# H18R2_Backend.net
KiCad netlist of a schematic drawn in Altium Designer
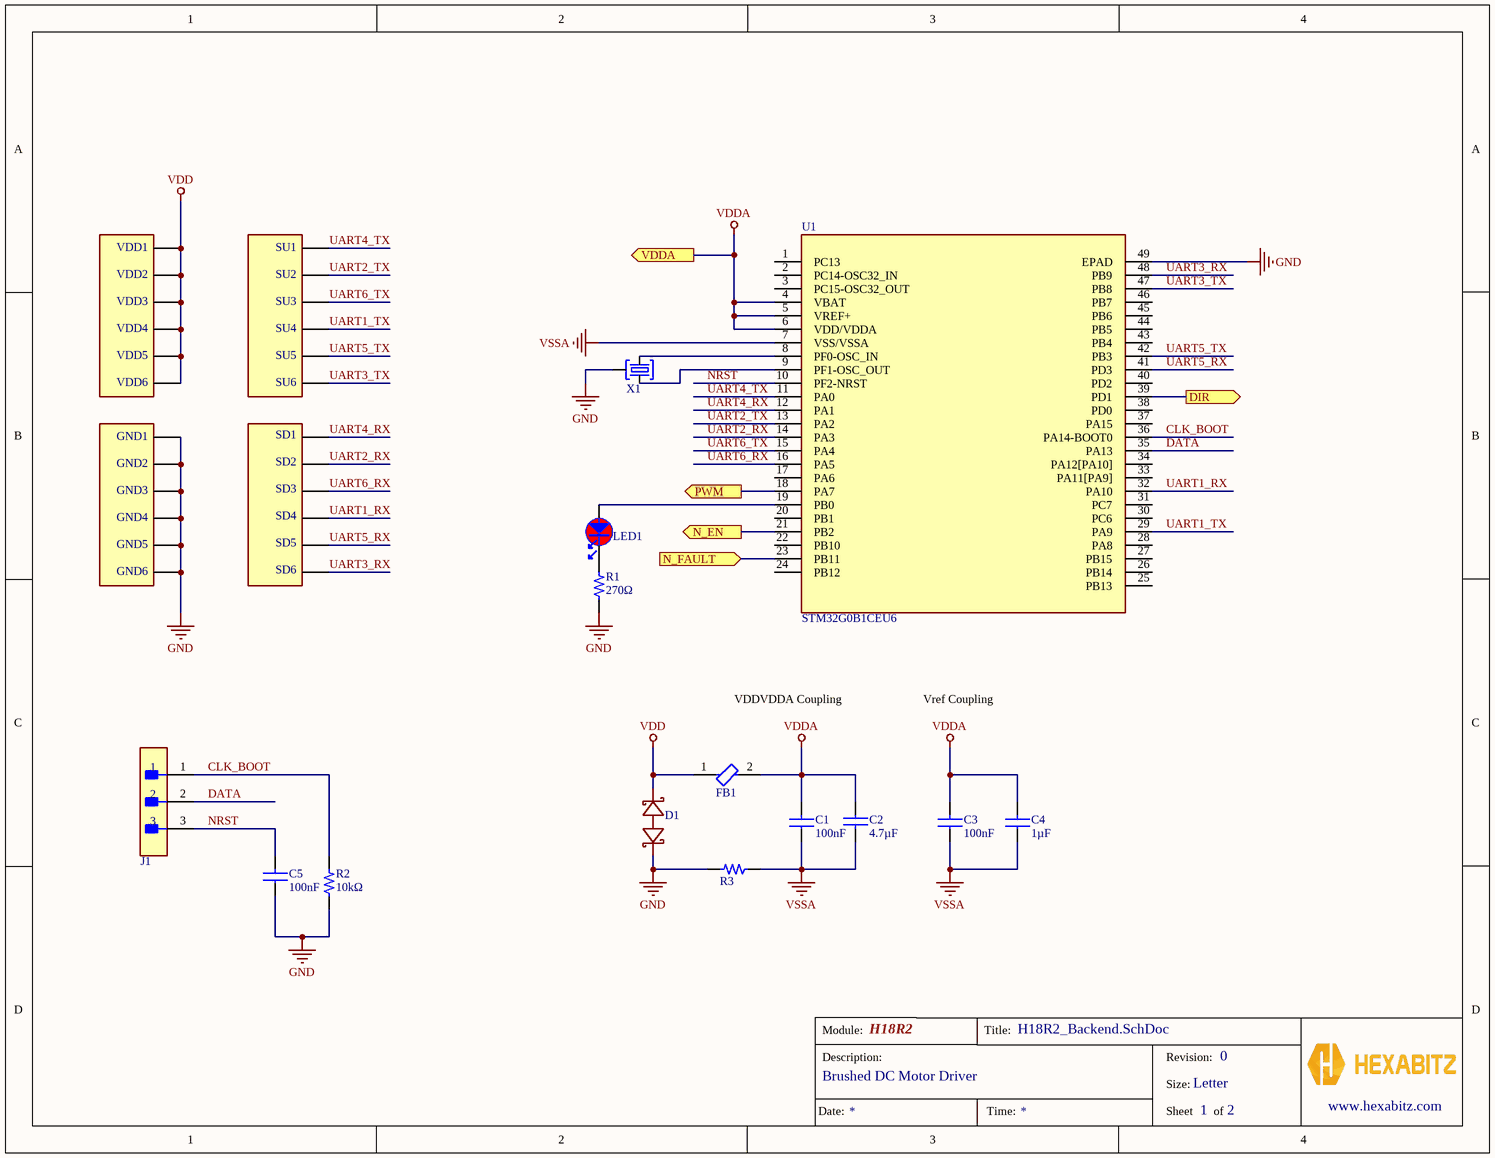
[diagram p0: H18R2_Backend.SchDoc]

(export (version "E")
  (design (tool "Eeschema 10.0.6"))
  (components
    (comp (ref "C1")
      (value "100nF")
      (footprint "C0603")
      (fields
        (field (name "MANUFACTURER") "Samsung Electro-Mechanics")
        (field (name "MANUFACTURER PART NUMBER") "CL10B104KA8NNNC")
        (field (name "TOLERANCE") "10%")
      )
      (libsource (lib "Hexabitz Altium Library") (part "generic Capacitor"))
    )
    (comp (ref "C2")
      (value "4.7µF")
      (footprint "C0805")
      (fields
        (field (name "MANUFACTURER") "Samsung Electro-Mechanics")
        (field (name "MANUFACTURER PART NUMBER") "CL21X475KAQNNNE")
        (field (name "TOLERANCE") "10%")
      )
      (libsource (lib "Hexabitz Altium Library") (part "generic Capacitor"))
    )
    (comp (ref "C3")
      (value "100nF")
      (footprint "C0603")
      (fields
        (field (name "MANUFACTURER") "Samsung Electro-Mechanics")
        (field (name "MANUFACTURER PART NUMBER") "CL10B104KA8NNNC")
        (field (name "TOLERANCE") "10%")
      )
      (libsource (lib "Hexabitz Altium Library") (part "generic Capacitor"))
    )
    (comp (ref "C4")
      (value "1µF")
      (footprint "C0805")
      (description "Ceramic Capacitor, Ceramic, 16V, 10% +Tol, 10% -Tol, X7R, 15% TC, 1uF, Surface Mount, 0805")
      (fields
        (field (name "MANUFACTURER") "Yageo Group")
        (field (name "MANUFACTURER PART NUMBER") "CC0805KKX7R7BB105")
      )
      (libsource (lib "Hexabitz Altium Library") (part "generic Capacitor"))
    )
    (comp (ref "C5")
      (value "100nF")
      (footprint "C0603")
      (fields
        (field (name "MANUFACTURER") "Samsung Electro-Mechanics")
        (field (name "MANUFACTURER PART NUMBER") "CL10B104KA8NNNC")
        (field (name "TOLERANCE") "10%")
      )
      (libsource (lib "Hexabitz Altium Library") (part "generic Capacitor"))
    )
    (comp (ref "D1")
      (value "CDSOD323-T03SC")
      (footprint "SOD2513X114N")
      (description "A 3V, 350W, bi-directional, standard capacitance, SOD323 pkg TVS Diode ¦ Bourns CDSOD323-T03SC")
      (fields (field (name "MANUFACTURER") "Bourns"))
      (libsource (lib "Hexabitz Altium Library") (part "CDSOD323-T03SC"))
    )
    (comp (ref "FB1")
      (value "MMZ1608Y300B")
      (footprint "FP-MMZ1608-0_8-MFG")
      (description "Ferrite Beads 0603 30ohms 1500mA Signal Line AEC-Q200")
      (fields
        (field (name "MANUFACTURER") "TDK")
        (field (name "MANUFACTURER PART NUMBER") "MMZ1608Y300BTD25")
      )
      (libsource (lib "Hexabitz Altium Library") (part "MMZ1608Y300B"))
    )
    (comp (ref "GND1")
      (value "HEXABIT_UART_PORT")
      (footprint "HEXABIT_POWER_PORT_D")
      (libsource (lib "hexabitz_connectors.Library") (part "HEXABIT_POWER_PORT_D"))
    )
    (comp (ref "GND2")
      (value "HEXABIT_UART_PORT")
      (footprint "HEXABIT_POWER_PORT_D")
      (libsource (lib "hexabitz_connectors.Library") (part "HEXABIT_POWER_PORT_D"))
    )
    (comp (ref "GND3")
      (value "HEXABIT_UART_PORT")
      (footprint "HEXABIT_POWER_PORT_D")
      (libsource (lib "hexabitz_connectors.Library") (part "HEXABIT_POWER_PORT_D"))
    )
    (comp (ref "GND4")
      (value "HEXABIT_UART_PORT")
      (footprint "HEXABIT_POWER_PORT_D")
      (libsource (lib "hexabitz_connectors.Library") (part "HEXABIT_POWER_PORT_D"))
    )
    (comp (ref "GND5")
      (value "HEXABIT_UART_PORT")
      (footprint "HEXABIT_POWER_PORT_D")
      (libsource (lib "hexabitz_connectors.Library") (part "HEXABIT_POWER_PORT_D"))
    )
    (comp (ref "GND6")
      (value "HEXABIT_UART_PORT")
      (footprint "HEXABIT_POWER_PORT_D")
      (libsource (lib "hexabitz_connectors.Library") (part "HEXABIT_POWER_PORT_D"))
    )
    (comp (ref "J1")
      (value "TSW-103-14-G-S")
      (footprint "FP-TSW-103-14-G-S-MFG")
      (description "CONN HEADER VERT 3POS 2.54MM")
      (fields (field (name "MANUFACTURER") "Samtec"))
      (libsource (lib "Altium Content Vault") (part "cd3439d6ef35ae5d9b27ec4fdd3e828"))
    )
    (comp (ref "LED1")
      (value "VLMS1300-GS08")
      (footprint "FP-6_541-5092_01-4-MFG")
      (description "LED Uni-Color Super Red 639nm 2-Pin Chip 0603(1608Metric) T/R")
      (fields (field (name "MANUFACTURER") "Vishay Semiconductors"))
      (libsource (lib "Hexabitz Altium Library") (part "VLMS1300-GS08"))
    )
    (comp (ref "R1")
      (value "270Ω")
      (footprint "R0603")
      (description "Res Thick Film 0603 270 Ohm 5% 0.1W(1/10W) ±200ppm/C Pad SMD Automotive T/R")
      (fields
        (field (name "MANUFACTURER") "Panasonic")
        (field (name "MANUFACTURER PART NUMBER") "ERJ-3GEYJ271V")
      )
      (libsource (lib "") (part "generic Resistor_2"))
    )
    (comp (ref "R2")
      (value "10kΩ")
      (footprint "R0603")
      (description "100mW Thick Film Resistors ±100ppm/℃ ±1% 10kΩ 0603 Chip Resistor - Surface Mount ROHS")
      (fields
        (field (name "MANUFACTURER") "Yageo Group")
        (field (name "MANUFACTURER PART NUMBER") "RC0603FR-0710KL")
      )
      (libsource (lib "Hexabitz Altium Library") (part "generic Resistor"))
    )
    (comp (ref "R3")
      (value "Manufacturer Part Number")
      (footprint "R0603")
      (libsource (lib "") (part "generic Resistor_1"))
    )
    (comp (ref "SD1")
      (value "HEXABIT_UART_PORT")
      (footprint "HEXABIT_UART_PORT_D")
      (libsource (lib "hexabitz_connectors.Library") (part "HEXABIT_UART_PORT_D"))
    )
    (comp (ref "SD2")
      (value "HEXABIT_UART_PORT")
      (footprint "HEXABIT_UART_PORT_D")
      (libsource (lib "hexabitz_connectors.Library") (part "HEXABIT_UART_PORT_D"))
    )
    (comp (ref "SD3")
      (value "HEXABIT_UART_PORT")
      (footprint "HEXABIT_UART_PORT_D")
      (libsource (lib "hexabitz_connectors.Library") (part "HEXABIT_UART_PORT_D"))
    )
    (comp (ref "SD4")
      (value "HEXABIT_UART_PORT")
      (footprint "HEXABIT_UART_PORT_D")
      (libsource (lib "hexabitz_connectors.Library") (part "HEXABIT_UART_PORT_D"))
    )
    (comp (ref "SD5")
      (value "HEXABIT_UART_PORT")
      (footprint "HEXABIT_UART_PORT_D")
      (libsource (lib "hexabitz_connectors.Library") (part "HEXABIT_UART_PORT_D"))
    )
    (comp (ref "SD6")
      (value "HEXABIT_UART_PORT")
      (footprint "HEXABIT_UART_PORT_D")
      (libsource (lib "hexabitz_connectors.Library") (part "HEXABIT_UART_PORT_D"))
    )
    (comp (ref "SU1")
      (value "HEXABIT_UART_PORT")
      (footprint "HEXABIT_UART_PORT_U")
      (libsource (lib "hexabitz_connectors.Library") (part "HEXABIT_UART_PORT_U"))
    )
    (comp (ref "SU2")
      (value "HEXABIT_UART_PORT")
      (footprint "HEXABIT_UART_PORT_U")
      (libsource (lib "hexabitz_connectors.Library") (part "HEXABIT_UART_PORT_U"))
    )
    (comp (ref "SU3")
      (value "HEXABIT_UART_PORT")
      (footprint "HEXABIT_UART_PORT_U")
      (libsource (lib "hexabitz_connectors.Library") (part "HEXABIT_UART_PORT_U"))
    )
    (comp (ref "SU4")
      (value "HEXABIT_UART_PORT")
      (footprint "HEXABIT_UART_PORT_U")
      (libsource (lib "hexabitz_connectors.Library") (part "HEXABIT_UART_PORT_U"))
    )
    (comp (ref "SU5")
      (value "HEXABIT_UART_PORT")
      (footprint "HEXABIT_UART_PORT_U")
      (libsource (lib "hexabitz_connectors.Library") (part "HEXABIT_UART_PORT_U"))
    )
    (comp (ref "SU6")
      (value "HEXABIT_UART_PORT")
      (footprint "HEXABIT_UART_PORT_U")
      (libsource (lib "hexabitz_connectors.Library") (part "HEXABIT_UART_PORT_U"))
    )
    (comp (ref "U1")
      (value "STM32G0B1CEU6")
      (footprint "QFN50P700X700X65-49N-D")
      (description "MCU 32-bit ARM Cortex M0+ RISC 512KB Flash 1.8V/2.5V/3.3V 48-Pin UFQFPN EP Tray")
      (fields
        (field (name "MANUFACTURER") "STMicroelectronics")
        (field (name "MANUFACTURER PART NUMBER") "STM32G0B1CEU6")
      )
      (libsource (lib "Hexabitz Altium Library") (part "STM32G0B1CEU6"))
    )
    (comp (ref "VDD1")
      (value "HEXABIT_UART_PORT")
      (footprint "HEXABIT_POWER_PORT_U")
      (libsource (lib "hexabitz_connectors.Library") (part "HEXABIT_POWER_PORT_U"))
    )
    (comp (ref "VDD2")
      (value "HEXABIT_UART_PORT")
      (footprint "HEXABIT_POWER_PORT_U")
      (libsource (lib "hexabitz_connectors.Library") (part "HEXABIT_POWER_PORT_U"))
    )
    (comp (ref "VDD3")
      (value "HEXABIT_UART_PORT")
      (footprint "HEXABIT_POWER_PORT_U")
      (libsource (lib "hexabitz_connectors.Library") (part "HEXABIT_POWER_PORT_U"))
    )
    (comp (ref "VDD4")
      (value "HEXABIT_UART_PORT")
      (footprint "HEXABIT_POWER_PORT_U")
      (libsource (lib "hexabitz_connectors.Library") (part "HEXABIT_POWER_PORT_U"))
    )
    (comp (ref "VDD5")
      (value "HEXABIT_UART_PORT")
      (footprint "HEXABIT_POWER_PORT_U")
      (libsource (lib "hexabitz_connectors.Library") (part "HEXABIT_POWER_PORT_U"))
    )
    (comp (ref "VDD6")
      (value "HEXABIT_UART_PORT")
      (footprint "HEXABIT_POWER_PORT_U")
      (libsource (lib "hexabitz_connectors.Library") (part "HEXABIT_POWER_PORT_U"))
    )
    (comp (ref "X1")
      (value "CSTCE8M00G52Z-R0")
      (footprint "XTALL_CSTCE8M00G52")
      (description "Ceramic Resonator 8MHz ±0.5% (Tol) ±0.2% (Stability) 10pF 40Ohm 3-Pin CSMD T/R")
      (fields (field (name "MANUFACTURER") "Murata") (field (name "TOLERANCE") "0.5%"))
      (libsource (lib "Hexabitz Altium Library") (part "CSTCE8M00G52Z-R0"))
    )
  )
  (nets
    (net (code "1") (name "/CLK_BOOT") (class "Default")
      (node (ref "J1") (pin "1") (pinfunction "1_1") (pintype "passive"))
      (node (ref "R2") (pin "1") (pinfunction "1_1") (pintype "passive"))
      (node (ref "U1") (pin "36") (pinfunction "PA14-BOOT0_36") (pintype "passive"))
    )
    (net (code "2") (name "/DATA") (class "Default")
      (node (ref "J1") (pin "2") (pinfunction "2_2") (pintype "passive"))
      (node (ref "U1") (pin "35") (pinfunction "PA13_35") (pintype "passive"))
    )
    (net (code "3") (name "/DIR") (class "Default")
      (node (ref "U1") (pin "39") (pinfunction "PD1_39") (pintype "passive"))
    )
    (net (code "4") (name "/NRST") (class "Default")
      (node (ref "C5") (pin "2") (pinfunction "2_2") (pintype "passive"))
      (node (ref "J1") (pin "3") (pinfunction "3_3") (pintype "passive"))
      (node (ref "U1") (pin "10") (pinfunction "PF2-NRST_10") (pintype "passive"))
    )
    (net (code "5") (name "/N_EN") (class "Default")
      (node (ref "U1") (pin "21") (pinfunction "PB2_21") (pintype "passive"))
    )
    (net (code "6") (name "/N_FAULT") (class "Default")
      (node (ref "U1") (pin "23") (pinfunction "PB11_23") (pintype "passive"))
    )
    (net (code "7") (name "/PWM") (class "Default")
      (node (ref "U1") (pin "18") (pinfunction "PA7_18") (pintype "passive"))
    )
    (net (code "8") (name "/UART1_RX") (class "Default")
      (node (ref "SD4") (pin "UART_D") (pinfunction "UART_D_UART_D") (pintype "passive"))
      (node (ref "U1") (pin "32") (pinfunction "PA10_32") (pintype "passive"))
    )
    (net (code "9") (name "/UART1_TX") (class "Default")
      (node (ref "SU4") (pin "UART_U") (pinfunction "UART_U_UART_U") (pintype "passive"))
      (node (ref "U1") (pin "29") (pinfunction "PA9_29") (pintype "passive"))
    )
    (net (code "10") (name "/UART2_RX") (class "Default")
      (node (ref "SD2") (pin "UART_D") (pinfunction "UART_D_UART_D") (pintype "passive"))
      (node (ref "U1") (pin "14") (pinfunction "PA3_14") (pintype "passive"))
    )
    (net (code "11") (name "/UART2_TX") (class "Default")
      (node (ref "SU2") (pin "UART_U") (pinfunction "UART_U_UART_U") (pintype "passive"))
      (node (ref "U1") (pin "13") (pinfunction "PA2_13") (pintype "passive"))
    )
    (net (code "12") (name "/UART3_RX") (class "Default")
      (node (ref "SD6") (pin "UART_D") (pinfunction "UART_D_UART_D") (pintype "passive"))
      (node (ref "U1") (pin "48") (pinfunction "PB9_48") (pintype "passive"))
    )
    (net (code "13") (name "/UART3_TX") (class "Default")
      (node (ref "SU6") (pin "UART_U") (pinfunction "UART_U_UART_U") (pintype "passive"))
      (node (ref "U1") (pin "47") (pinfunction "PB8_47") (pintype "passive"))
    )
    (net (code "14") (name "/UART4_RX") (class "Default")
      (node (ref "SD1") (pin "UART_D") (pinfunction "UART_D_UART_D") (pintype "passive"))
      (node (ref "U1") (pin "12") (pinfunction "PA1_12") (pintype "passive"))
    )
    (net (code "15") (name "/UART4_TX") (class "Default")
      (node (ref "SU1") (pin "UART_U") (pinfunction "UART_U_UART_U") (pintype "passive"))
      (node (ref "U1") (pin "11") (pinfunction "PA0_11") (pintype "passive"))
    )
    (net (code "16") (name "/UART5_RX") (class "Default")
      (node (ref "SD5") (pin "UART_D") (pinfunction "UART_D_UART_D") (pintype "passive"))
      (node (ref "U1") (pin "41") (pinfunction "PD3_41") (pintype "passive"))
    )
    (net (code "17") (name "/UART5_TX") (class "Default")
      (node (ref "SU5") (pin "UART_U") (pinfunction "UART_U_UART_U") (pintype "passive"))
      (node (ref "U1") (pin "42") (pinfunction "PB3_42") (pintype "passive"))
    )
    (net (code "18") (name "/UART6_RX") (class "Default")
      (node (ref "SD3") (pin "UART_D") (pinfunction "UART_D_UART_D") (pintype "passive"))
      (node (ref "U1") (pin "16") (pinfunction "PA5_16") (pintype "passive"))
    )
    (net (code "19") (name "/UART6_TX") (class "Default")
      (node (ref "SU3") (pin "UART_U") (pinfunction "UART_U_UART_U") (pintype "passive"))
      (node (ref "U1") (pin "15") (pinfunction "PA4_15") (pintype "passive"))
    )
    (net (code "20") (name "GND") (class "Default")
      (node (ref "C5") (pin "1") (pinfunction "1_1") (pintype "passive"))
      (node (ref "D1") (pin "1") (pinfunction "A_1") (pintype "passive"))
      (node (ref "GND1") (pin "Pwr_D") (pinfunction "Pwr_D_Pwr_D") (pintype "passive"))
      (node (ref "GND2") (pin "Pwr_D") (pinfunction "Pwr_D_Pwr_D") (pintype "passive"))
      (node (ref "GND3") (pin "Pwr_D") (pinfunction "Pwr_D_Pwr_D") (pintype "passive"))
      (node (ref "GND4") (pin "Pwr_D") (pinfunction "Pwr_D_Pwr_D") (pintype "passive"))
      (node (ref "GND5") (pin "Pwr_D") (pinfunction "Pwr_D_Pwr_D") (pintype "passive"))
      (node (ref "GND6") (pin "Pwr_D") (pinfunction "Pwr_D_Pwr_D") (pintype "passive"))
      (node (ref "R1") (pin "1") (pinfunction "1_1") (pintype "passive"))
      (node (ref "R2") (pin "2") (pinfunction "2_2") (pintype "passive"))
      (node (ref "R3") (pin "1") (pinfunction "1_1") (pintype "passive"))
      (node (ref "U1") (pin "49") (pinfunction "EPAD_49") (pintype "passive"))
      (node (ref "X1") (pin "P$2") (pinfunction "2_P$2") (pintype "passive"))
    )
    (net (code "21") (name "Net-(LED1-Pad1)") (class "Default")
      (node (ref "LED1") (pin "1") (pintype "passive"))
      (node (ref "R1") (pin "2") (pinfunction "2_2") (pintype "passive"))
    )
    (net (code "22") (name "Net-(U1-PB0)") (class "Default")
      (node (ref "LED1") (pin "2") (pintype "passive"))
      (node (ref "U1") (pin "19") (pinfunction "PB0_19") (pintype "passive"))
    )
    (net (code "23") (name "Net-(U1-PF0-OSC_IN)") (class "Default")
      (node (ref "U1") (pin "8") (pinfunction "PF0-OSC_IN_8") (pintype "passive"))
      (node (ref "X1") (pin "P$3") (pinfunction "3_P$3") (pintype "passive"))
    )
    (net (code "24") (name "Net-(U1-PF1-OSC_OUT)") (class "Default")
      (node (ref "U1") (pin "9") (pinfunction "PF1-OSC_OUT_9") (pintype "passive"))
      (node (ref "X1") (pin "P$1") (pinfunction "1_P$1") (pintype "passive"))
    )
    (net (code "25") (name "VDD") (class "Default")
      (node (ref "D1") (pin "2") (pinfunction "C_2") (pintype "passive"))
      (node (ref "FB1") (pin "1") (pinfunction "1_1") (pintype "passive"))
      (node (ref "VDD1") (pin "Pwr_U") (pinfunction "Pwr_U_Pwr_U") (pintype "passive"))
      (node (ref "VDD2") (pin "Pwr_U") (pinfunction "Pwr_U_Pwr_U") (pintype "passive"))
      (node (ref "VDD3") (pin "Pwr_U") (pinfunction "Pwr_U_Pwr_U") (pintype "passive"))
      (node (ref "VDD4") (pin "Pwr_U") (pinfunction "Pwr_U_Pwr_U") (pintype "passive"))
      (node (ref "VDD5") (pin "Pwr_U") (pinfunction "Pwr_U_Pwr_U") (pintype "passive"))
      (node (ref "VDD6") (pin "Pwr_U") (pinfunction "Pwr_U_Pwr_U") (pintype "passive"))
    )
    (net (code "26") (name "VDDA") (class "Default")
      (node (ref "C1") (pin "2") (pinfunction "2_2") (pintype "passive"))
      (node (ref "C2") (pin "1") (pinfunction "1_1") (pintype "passive"))
      (node (ref "C3") (pin "2") (pinfunction "2_2") (pintype "passive"))
      (node (ref "C4") (pin "2") (pinfunction "2_2") (pintype "passive"))
      (node (ref "FB1") (pin "2") (pinfunction "2_2") (pintype "passive"))
      (node (ref "U1") (pin "4") (pinfunction "VBAT_4") (pintype "passive"))
      (node (ref "U1") (pin "5") (pinfunction "VREF+_5") (pintype "passive"))
      (node (ref "U1") (pin "6") (pinfunction "VDD/VDDA_6") (pintype "passive"))
    )
    (net (code "27") (name "VSSA") (class "Default")
      (node (ref "C1") (pin "1") (pinfunction "1_1") (pintype "passive"))
      (node (ref "C2") (pin "2") (pinfunction "2_2") (pintype "passive"))
      (node (ref "C3") (pin "1") (pinfunction "1_1") (pintype "passive"))
      (node (ref "C4") (pin "1") (pinfunction "1_1") (pintype "passive"))
      (node (ref "R3") (pin "2") (pinfunction "2_2") (pintype "passive"))
      (node (ref "U1") (pin "7") (pinfunction "VSS/VSSA_7") (pintype "passive"))
    )
    (net (code "28") (name "unconnected-(U1-PA6-Pad17)") (class "Default")
      (node (ref "U1") (pin "17") (pinfunction "PA6_17") (pintype "passive"))
    )
    (net (code "29") (name "unconnected-(U1-PA8-Pad28)") (class "Default")
      (node (ref "U1") (pin "28") (pinfunction "PA8_28") (pintype "passive"))
    )
    (net (code "30") (name "unconnected-(U1-PA11[PA9]-Pad33)") (class "Default")
      (node (ref "U1") (pin "33") (pinfunction "PA11[PA9]_33") (pintype "passive"))
    )
    (net (code "31") (name "unconnected-(U1-PA12[PA10]-Pad34)") (class "Default")
      (node (ref "U1") (pin "34") (pinfunction "PA12[PA10]_34") (pintype "passive"))
    )
    (net (code "32") (name "unconnected-(U1-PA15-Pad37)") (class "Default")
      (node (ref "U1") (pin "37") (pinfunction "PA15_37") (pintype "passive"))
    )
    (net (code "33") (name "unconnected-(U1-PB1-Pad20)") (class "Default")
      (node (ref "U1") (pin "20") (pinfunction "PB1_20") (pintype "passive"))
    )
    (net (code "34") (name "unconnected-(U1-PB4-Pad43)") (class "Default")
      (node (ref "U1") (pin "43") (pinfunction "PB4_43") (pintype "passive"))
    )
    (net (code "35") (name "unconnected-(U1-PB5-Pad44)") (class "Default")
      (node (ref "U1") (pin "44") (pinfunction "PB5_44") (pintype "passive"))
    )
    (net (code "36") (name "unconnected-(U1-PB6-Pad45)") (class "Default")
      (node (ref "U1") (pin "45") (pinfunction "PB6_45") (pintype "passive"))
    )
    (net (code "37") (name "unconnected-(U1-PB7-Pad46)") (class "Default")
      (node (ref "U1") (pin "46") (pinfunction "PB7_46") (pintype "passive"))
    )
    (net (code "38") (name "unconnected-(U1-PB10-Pad22)") (class "Default")
      (node (ref "U1") (pin "22") (pinfunction "PB10_22") (pintype "passive"))
    )
    (net (code "39") (name "unconnected-(U1-PB12-Pad24)") (class "Default")
      (node (ref "U1") (pin "24") (pinfunction "PB12_24") (pintype "passive"))
    )
    (net (code "40") (name "unconnected-(U1-PB13-Pad25)") (class "Default")
      (node (ref "U1") (pin "25") (pinfunction "PB13_25") (pintype "passive"))
    )
    (net (code "41") (name "unconnected-(U1-PB14-Pad26)") (class "Default")
      (node (ref "U1") (pin "26") (pinfunction "PB14_26") (pintype "passive"))
    )
    (net (code "42") (name "unconnected-(U1-PB15-Pad27)") (class "Default")
      (node (ref "U1") (pin "27") (pinfunction "PB15_27") (pintype "passive"))
    )
    (net (code "43") (name "unconnected-(U1-PC6-Pad30)") (class "Default")
      (node (ref "U1") (pin "30") (pinfunction "PC6_30") (pintype "passive"))
    )
    (net (code "44") (name "unconnected-(U1-PC7-Pad31)") (class "Default")
      (node (ref "U1") (pin "31") (pinfunction "PC7_31") (pintype "passive"))
    )
    (net (code "45") (name "unconnected-(U1-PC13-Pad1)") (class "Default")
      (node (ref "U1") (pin "1") (pinfunction "PC13_1") (pintype "passive"))
    )
    (net (code "46") (name "unconnected-(U1-PC14-OSC32_IN-Pad2)") (class "Default")
      (node (ref "U1") (pin "2") (pinfunction "PC14-OSC32_IN_2") (pintype "passive"))
    )
    (net (code "47") (name "unconnected-(U1-PC15-OSC32_OUT-Pad3)") (class "Default")
      (node (ref "U1") (pin "3") (pinfunction "PC15-OSC32_OUT_3") (pintype "passive"))
    )
    (net (code "48") (name "unconnected-(U1-PD0-Pad38)") (class "Default")
      (node (ref "U1") (pin "38") (pinfunction "PD0_38") (pintype "passive"))
    )
    (net (code "49") (name "unconnected-(U1-PD2-Pad40)") (class "Default")
      (node (ref "U1") (pin "40") (pinfunction "PD2_40") (pintype "passive"))
    )
  )
)
